# Power_Input.net
KiCad netlist of a schematic drawn in Altium Designer
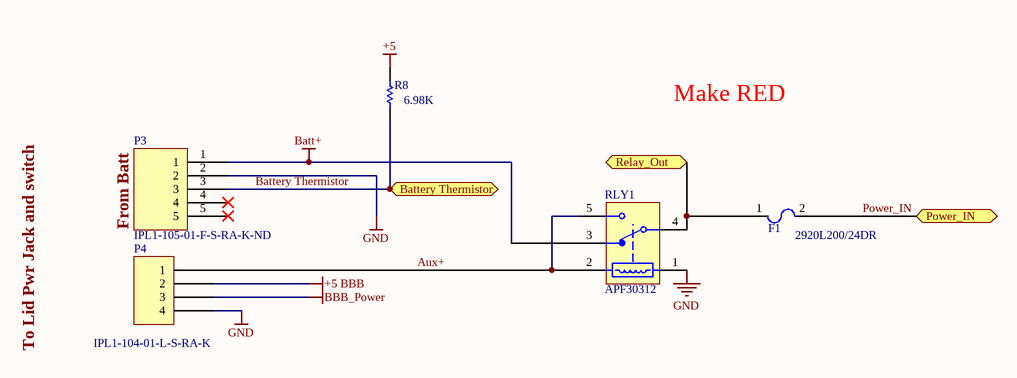
[diagram p0: Power_Input.SchDoc]

(export (version "E")
  (design (tool "Eeschema 10.0.6"))
  (components
    (comp (ref "F1")
      (value "PCT")
      (footprint "CAPC7451X12N")
      (libsource (lib "ZLS_Schematic_lib") (part "PCT"))
    )
    (comp (ref "P3")
      (value "IPL1-105-01-F-S-RA")
      (footprint "IPL1-105-01-F-S-RA")
      (fields (field (name "SUPPLIER PART NUMBER 1") "IPL1-105-01-F-S-RA-K-ND"))
      (libsource (lib "ZLS_Schematic_lib") (part "IPL1-105-01-F-S-RA"))
    )
    (comp (ref "P4")
      (value "IPL1-104-01-L-S-RA-K")
      (footprint "IPL1-104-01-L-S-RA-K")
      (fields
        (field (name "MANUFACTURER") "Samtec Inc.")
        (field (name "MANUFACTURER PART NUMBER") "IPL1-104-01-L-S-RA-K")
      )
      (libsource (lib "ZLS_Schematic_lib") (part "IPL1-104-01-L-S-RA-K"))
    )
    (comp (ref "R8")
      (value "6.98K")
      (footprint "RESC0402(1005)_L")
      (description "RES SMD 6.98K OHM 1% 1/16W 0402")
      (fields
        (field (name "MANUFACTURER") "Yageo")
        (field (name "MANUFACTURER PART NUMBER") "RC0402FR-076K98L")
      )
      (libsource (lib "Altium Content Vault") (part "CMP-1011-00927-1"))
    )
    (comp (ref "RLY1")
      (value "APF30312")
      (footprint "PNSC-PF-5-2800x500x1500_V")
      (fields (field (name "MANUFACTURER") "Panasonic"))
      (libsource (lib "Altium Content Vault") (part "PNSC-APF30312-PF-5-2800x500x1500-5"))
    )
  )
  (nets
    (net (code "1") (name "+5") (class "Default")
      (node (ref "R8") (pin "2") (pinfunction "2_2") (pintype "passive"))
    )
    (net (code "2") (name "+5 BBB") (class "Default")
      (node (ref "P4") (pin "2") (pinfunction "2_2") (pintype "passive"))
    )
    (net (code "3") (name "/Aux+") (class "Default")
      (node (ref "P4") (pin "1") (pinfunction "1_1") (pintype "passive"))
      (node (ref "RLY1") (pin "2") (pinfunction "2_2") (pintype "passive"))
      (node (ref "RLY1") (pin "5") (pinfunction "NO_5") (pintype "passive"))
    )
    (net (code "4") (name "/Battery Thermistor") (class "Default")
      (node (ref "P3") (pin "3") (pinfunction "3_3") (pintype "passive"))
      (node (ref "R8") (pin "1") (pinfunction "1_1") (pintype "passive"))
    )
    (net (code "5") (name "/Power_IN") (class "Default")
      (node (ref "F1") (pin "2") (pinfunction "2_2") (pintype "passive"))
    )
    (net (code "6") (name "/Relay_Out") (class "Default")
      (node (ref "F1") (pin "1") (pinfunction "1_1") (pintype "passive"))
      (node (ref "RLY1") (pin "4") (pinfunction "COM_4") (pintype "passive"))
    )
    (net (code "7") (name "BBB_Power") (class "Default")
      (node (ref "P4") (pin "3") (pinfunction "3_3") (pintype "passive"))
    )
    (net (code "8") (name "Batt+") (class "Default")
      (node (ref "P3") (pin "1") (pinfunction "1_1") (pintype "passive"))
      (node (ref "RLY1") (pin "3") (pinfunction "NC_3") (pintype "passive"))
    )
    (net (code "9") (name "GND") (class "Default")
      (node (ref "P3") (pin "2") (pinfunction "2_2") (pintype "passive"))
      (node (ref "P4") (pin "4") (pinfunction "4_4") (pintype "passive"))
      (node (ref "RLY1") (pin "1") (pinfunction "1_1") (pintype "passive"))
    )
    (net (code "10") (name "unconnected-(P3-Pad4)") (class "Default")
      (node (ref "P3") (pin "4") (pinfunction "4_4") (pintype "passive+no_connect"))
    )
    (net (code "11") (name "unconnected-(P3-Pad5)") (class "Default")
      (node (ref "P3") (pin "5") (pinfunction "5_5") (pintype "passive+no_connect"))
    )
  )
)
